# PowerNode.net
KiCad netlist of a schematic drawn in EAGLE
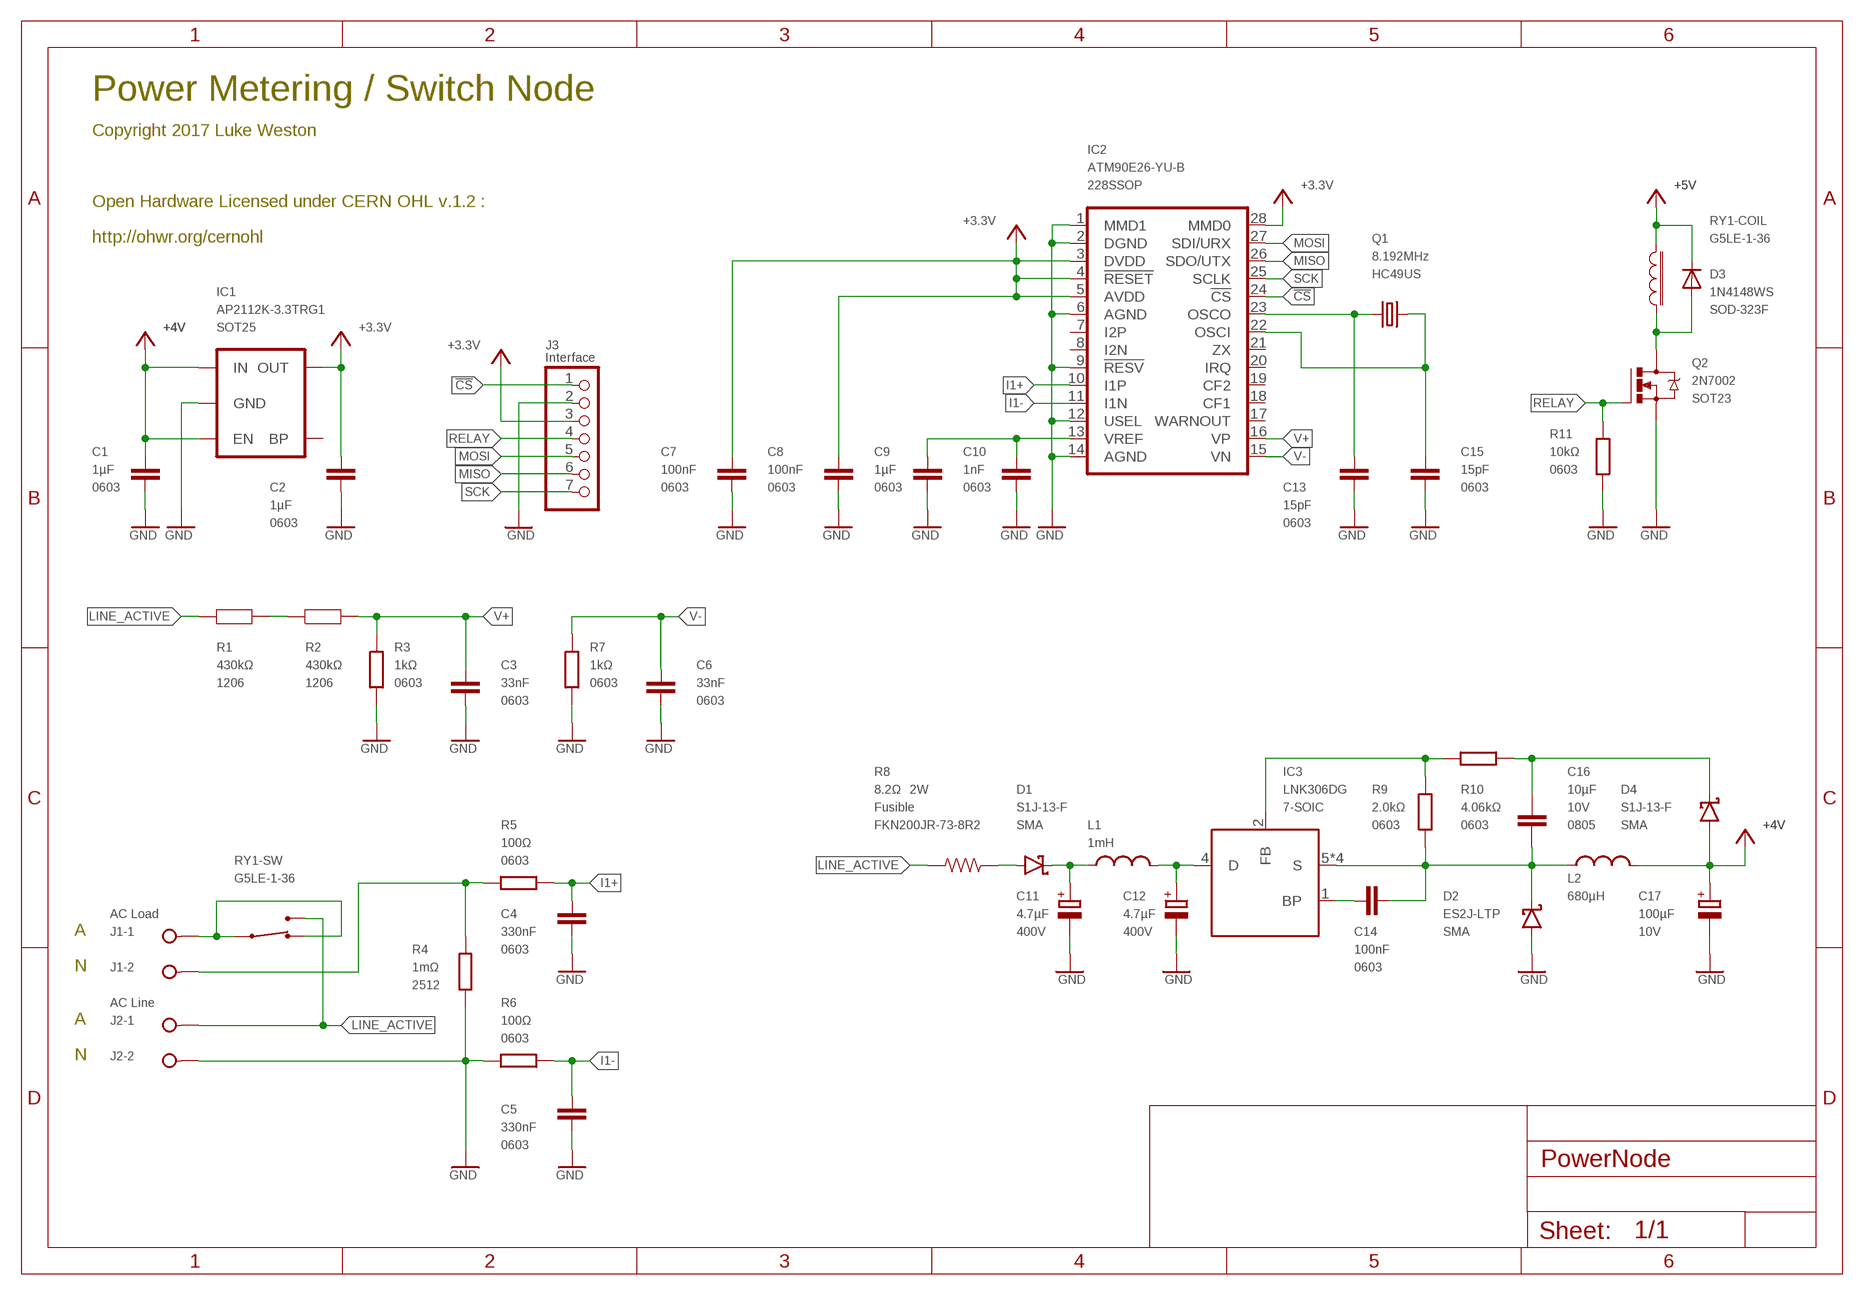
[diagram p0: schematic, sheet 1]

(export (version "E")
  (design (tool "Eeschema 10.0.6"))
  (components
    (comp (ref "C1")
      (value "1µF")
      (footprint "eagle-import:0603")
      (fields (field (name "PACKAGE") "0603"))
      (libsource (lib "eagle-import") (part "C0603"))
    )
    (comp (ref "C2")
      (value "1µF")
      (footprint "eagle-import:0603")
      (fields (field (name "PACKAGE") "0603"))
      (libsource (lib "eagle-import") (part "C0603"))
    )
    (comp (ref "C3")
      (value "33nF")
      (footprint "eagle-import:0603")
      (fields (field (name "PACKAGE") "0603"))
      (libsource (lib "eagle-import") (part "C0603"))
    )
    (comp (ref "C4")
      (value "330nF")
      (footprint "eagle-import:0603")
      (fields (field (name "PACKAGE") "0603"))
      (libsource (lib "eagle-import") (part "C0603"))
    )
    (comp (ref "C5")
      (value "330nF")
      (footprint "eagle-import:0603")
      (fields (field (name "PACKAGE") "0603"))
      (libsource (lib "eagle-import") (part "C0603"))
    )
    (comp (ref "C6")
      (value "33nF")
      (footprint "eagle-import:0603")
      (fields (field (name "PACKAGE") "0603"))
      (libsource (lib "eagle-import") (part "C0603"))
    )
    (comp (ref "C7")
      (value "100nF")
      (footprint "eagle-import:0603")
      (fields (field (name "PACKAGE") "0603"))
      (libsource (lib "eagle-import") (part "C0603"))
    )
    (comp (ref "C8")
      (value "100nF")
      (footprint "eagle-import:0603")
      (fields (field (name "PACKAGE") "0603"))
      (libsource (lib "eagle-import") (part "C0603"))
    )
    (comp (ref "C9")
      (value "1µF")
      (footprint "eagle-import:0603")
      (fields (field (name "PACKAGE") "0603"))
      (libsource (lib "eagle-import") (part "C0603"))
    )
    (comp (ref "C10")
      (value "1nF")
      (footprint "eagle-import:0603")
      (fields (field (name "PACKAGE") "0603"))
      (libsource (lib "eagle-import") (part "C0603"))
    )
    (comp (ref "C11")
      (value "4.7µF")
      (footprint "eagle-import:ELECTRO-LARGE")
      (fields (field (name "VOLTAGE") "400V"))
      (libsource (lib "eagle-import") (part "ELECTROLYTIC3.5MM"))
    )
    (comp (ref "C12")
      (value "4.7µF")
      (footprint "eagle-import:ELECTRO-LARGE")
      (fields (field (name "VOLTAGE") "400V"))
      (libsource (lib "eagle-import") (part "ELECTROLYTIC3.5MM"))
    )
    (comp (ref "C13")
      (value "15pF")
      (footprint "eagle-import:0603")
      (fields (field (name "PACKAGE") "0603"))
      (libsource (lib "eagle-import") (part "C0603"))
    )
    (comp (ref "C14")
      (value "100nF")
      (footprint "eagle-import:0603")
      (fields (field (name "PACKAGE") "0603"))
      (libsource (lib "eagle-import") (part "C0603"))
    )
    (comp (ref "C15")
      (value "15pF")
      (footprint "eagle-import:0603")
      (fields (field (name "PACKAGE") "0603"))
      (libsource (lib "eagle-import") (part "C0603"))
    )
    (comp (ref "C16")
      (value "10µF")
      (footprint "eagle-import:0805")
      (fields (field (name "PACKAGE") "0805") (field (name "VOLTAGE") "10V"))
      (libsource (lib "eagle-import") (part "CAP0805"))
    )
    (comp (ref "C17")
      (value "100µF")
      (footprint "eagle-import:ELECTRO-SMALL")
      (fields (field (name "VOLTAGE") "10V"))
      (libsource (lib "eagle-import") (part "ELECTROLYTIC2MM"))
    )
    (comp (ref "D1")
      (value "S1J-13-F")
      (footprint "eagle-import:SMA")
      (fields (field (name "PACKAGE") "SMA"))
      (libsource (lib "eagle-import") (part "SCHOTTKY-SMA"))
    )
    (comp (ref "D2")
      (value "ES2J-LTP")
      (footprint "eagle-import:SMA")
      (fields (field (name "PACKAGE") "SMA"))
      (libsource (lib "eagle-import") (part "SCHOTTKY-SMA"))
    )
    (comp (ref "D3")
      (value "1N4148WS")
      (footprint "eagle-import:SOD-323")
      (fields (field (name "PACKAGE") "SOD-323F"))
      (libsource (lib "eagle-import") (part "DIODESOD"))
    )
    (comp (ref "D4")
      (value "S1J-13-F")
      (footprint "eagle-import:SMA")
      (fields (field (name "PACKAGE") "SMA"))
      (libsource (lib "eagle-import") (part "SCHOTTKY-SMA"))
    )
    (comp (ref "IC1")
      (value "AP2112K-3.3TRG1")
      (footprint "eagle-import:SOT23-5")
      (fields (field (name "PACKAGE") "SOT25"))
      (libsource (lib "eagle-import") (part "V_REG_LDOSMD"))
    )
    (comp (ref "IC2")
      (value "ATM90E26-YU-B")
      (footprint "eagle-import:SSOP-28")
      (fields (field (name "PACKAGE") "228SSOP"))
      (libsource (lib "eagle-import") (part "ATM90E26"))
    )
    (comp (ref "IC3")
      (value "LNK306DG")
      (footprint "eagle-import:SO-8C")
      (fields (field (name "PACKAGE") "7-SOIC"))
      (libsource (lib "eagle-import") (part "LNK304"))
    )
    (comp (ref "J1")
      (value "AC Load")
      (footprint "eagle-import:W237-132")
      (libsource (lib "eagle-import") (part "W237-02P"))
    )
    (comp (ref "J2")
      (value "AC Line")
      (footprint "eagle-import:W237-132")
      (libsource (lib "eagle-import") (part "W237-02P"))
    )
    (comp (ref "J3")
      (value "Interface")
      (footprint "eagle-import:1X07")
      (libsource (lib "eagle-import") (part "PINHD-1X7"))
    )
    (comp (ref "L1")
      (value "1mH")
      (footprint "eagle-import:RLB0608")
      (libsource (lib "eagle-import") (part "LRLB0608"))
    )
    (comp (ref "L2")
      (value "680µH")
      (footprint "eagle-import:RLB0914")
      (libsource (lib "eagle-import") (part "LRLB0914"))
    )
    (comp (ref "Q1")
      (value "8.192MHz")
      (footprint "eagle-import:HC49_S")
      (fields (field (name "PACKAGE") "HC49US") (field (name "PARTNO") "9B-4.096MBBK-B"))
      (libsource (lib "eagle-import") (part "CRYSTALHC49S"))
    )
    (comp (ref "Q2")
      (value "2N7002")
      (footprint "eagle-import:SOT23-3")
      (fields (field (name "PACKAGE") "SOT23"))
      (libsource (lib "eagle-import") (part "2N7002"))
    )
    (comp (ref "R1")
      (value "430kΩ")
      (footprint "eagle-import:1206")
      (fields (field (name "PACKAGE") "1206") (field (name "POWER") "1/4W") (field (name "TOLERANCE") "1%"))
      (libsource (lib "eagle-import") (part "RESISTOR1206"))
    )
    (comp (ref "R2")
      (value "430kΩ")
      (footprint "eagle-import:1206")
      (fields (field (name "PACKAGE") "1206") (field (name "POWER") "1/4W") (field (name "TOLERANCE") "1%"))
      (libsource (lib "eagle-import") (part "RESISTOR1206"))
    )
    (comp (ref "R3")
      (value "1kΩ")
      (footprint "eagle-import:0603")
      (fields (field (name "PACKAGE") "0603"))
      (libsource (lib "eagle-import") (part "R0603"))
    )
    (comp (ref "R4")
      (value "1mΩ")
      (footprint "eagle-import:R2512")
      (fields (field (name "PACKAGE") "2512") (field (name "POWER") "1W") (field (name "TOLERANCE") "1%"))
      (libsource (lib "eagle-import") (part "R-EU_R2512"))
    )
    (comp (ref "R5")
      (value "100Ω")
      (footprint "eagle-import:0603")
      (fields (field (name "PACKAGE") "0603"))
      (libsource (lib "eagle-import") (part "R0603"))
    )
    (comp (ref "R6")
      (value "100Ω")
      (footprint "eagle-import:0603")
      (fields (field (name "PACKAGE") "0603"))
      (libsource (lib "eagle-import") (part "R0603"))
    )
    (comp (ref "R7")
      (value "1kΩ")
      (footprint "eagle-import:0603")
      (fields (field (name "PACKAGE") "0603"))
      (libsource (lib "eagle-import") (part "R0603"))
    )
    (comp (ref "R8")
      (value "8.2Ω")
      (footprint "eagle-import:FKN200JR-73")
      (fields
        (field (name "FOO") "Fusible")
        (field (name "ID") "FKN200JR-73-8R2")
        (field (name "POWER") "2W")
      )
      (libsource (lib "eagle-import") (part "RESISTORFKN200JR-73"))
    )
    (comp (ref "R9")
      (value "2.0kΩ")
      (footprint "eagle-import:0603")
      (fields (field (name "PACKAGE") "0603"))
      (libsource (lib "eagle-import") (part "R0603"))
    )
    (comp (ref "R10")
      (value "4.06kΩ")
      (footprint "eagle-import:0603")
      (fields (field (name "PACKAGE") "0603"))
      (libsource (lib "eagle-import") (part "R0603"))
    )
    (comp (ref "R11")
      (value "10kΩ")
      (footprint "eagle-import:0603")
      (fields (field (name "PACKAGE") "0603"))
      (libsource (lib "eagle-import") (part "R0603"))
    )
    (comp (ref "RY1")
      (value "G5LE-1-36")
      (footprint "eagle-import:G5LE")
      (libsource (lib "eagle-import") (part "G5LE"))
    )
  )
  (nets
    (net (code "1") (name "+3.3V") (class "Default")
      (node (ref "C2") (pin "1") (pinfunction "1_1") (pintype "passive"))
      (node (ref "C7") (pin "2") (pinfunction "2_2") (pintype "passive"))
      (node (ref "C8") (pin "2") (pinfunction "2_2") (pintype "passive"))
      (node (ref "IC1") (pin "5") (pinfunction "OUT_5") (pintype "passive"))
      (node (ref "IC2") (pin "28") (pinfunction "MMD0_28") (pintype "input"))
      (node (ref "IC2") (pin "3") (pinfunction "DVDD_3") (pintype "power_in"))
      (node (ref "IC2") (pin "4") (pinfunction "~{RESET}_4") (pintype "input"))
      (node (ref "IC2") (pin "5") (pinfunction "AVDD_5") (pintype "power_in"))
      (node (ref "J3") (pin "3") (pinfunction "3_3") (pintype "passive"))
    )
    (net (code "2") (name "/+4V") (class "Default")
      (node (ref "C1") (pin "1") (pinfunction "1_1") (pintype "passive"))
      (node (ref "C17") (pin "+") (pinfunction "+_+") (pintype "passive"))
      (node (ref "D3") (pin "1") (pinfunction "C_1") (pintype "passive"))
      (node (ref "D4") (pin "A") (pinfunction "A_A") (pintype "passive"))
      (node (ref "IC1") (pin "1") (pinfunction "IN_1") (pintype "input"))
      (node (ref "IC1") (pin "3") (pinfunction "EN_3") (pintype "input"))
      (node (ref "L2") (pin "2") (pinfunction "2_2") (pintype "bidirectional"))
      (node (ref "RY1") (pin "COIL1") (pinfunction "1_COIL1") (pintype "bidirectional"))
    )
    (net (code "3") (name "/GND") (class "Default")
      (node (ref "C1") (pin "2") (pinfunction "2_2") (pintype "passive"))
      (node (ref "C10") (pin "1") (pinfunction "1_1") (pintype "passive"))
      (node (ref "C11") (pin "-") (pinfunction "-_-") (pintype "passive"))
      (node (ref "C12") (pin "-") (pinfunction "-_-") (pintype "passive"))
      (node (ref "C13") (pin "1") (pinfunction "1_1") (pintype "passive"))
      (node (ref "C15") (pin "1") (pinfunction "1_1") (pintype "passive"))
      (node (ref "C17") (pin "-") (pinfunction "-_-") (pintype "passive"))
      (node (ref "C2") (pin "2") (pinfunction "2_2") (pintype "passive"))
      (node (ref "C3") (pin "1") (pinfunction "1_1") (pintype "passive"))
      (node (ref "C4") (pin "1") (pinfunction "1_1") (pintype "passive"))
      (node (ref "C5") (pin "1") (pinfunction "1_1") (pintype "passive"))
      (node (ref "C6") (pin "1") (pinfunction "1_1") (pintype "passive"))
      (node (ref "C7") (pin "1") (pinfunction "1_1") (pintype "passive"))
      (node (ref "C8") (pin "1") (pinfunction "1_1") (pintype "passive"))
      (node (ref "C9") (pin "2") (pinfunction "2_2") (pintype "passive"))
      (node (ref "D2") (pin "A") (pinfunction "A_A") (pintype "passive"))
      (node (ref "IC1") (pin "2") (pinfunction "GND_2") (pintype "input"))
      (node (ref "IC2") (pin "1") (pinfunction "MMD1_1") (pintype "input"))
      (node (ref "IC2") (pin "12") (pinfunction "USEL_12") (pintype "input"))
      (node (ref "IC2") (pin "14") (pinfunction "AGND_14") (pintype "power_in"))
      (node (ref "IC2") (pin "2") (pinfunction "DGND_2") (pintype "power_in"))
      (node (ref "IC2") (pin "6") (pinfunction "AGND_6") (pintype "power_in"))
      (node (ref "IC2") (pin "9") (pinfunction "~{RESV}_9") (pintype "input"))
      (node (ref "J2") (pin "2") (pinfunction "KL_2") (pintype "passive"))
      (node (ref "J3") (pin "2") (pinfunction "2_2") (pintype "passive"))
      (node (ref "Q2") (pin "2") (pinfunction "S_2") (pintype "passive"))
      (node (ref "R11") (pin "1") (pinfunction "1_1") (pintype "passive"))
      (node (ref "R3") (pin "2") (pinfunction "2_2") (pintype "passive"))
      (node (ref "R4") (pin "1") (pinfunction "1_1") (pintype "passive"))
      (node (ref "R6") (pin "2") (pinfunction "2_2") (pintype "passive"))
      (node (ref "R7") (pin "2") (pinfunction "2_2") (pintype "passive"))
    )
    (net (code "4") (name "/~{CS}") (class "Default")
      (node (ref "IC2") (pin "24") (pinfunction "~{CS}_24") (pintype "input"))
      (node (ref "J3") (pin "1") (pinfunction "1_1") (pintype "passive"))
    )
    (net (code "5") (name "I1+") (class "Default")
      (node (ref "C4") (pin "2") (pinfunction "2_2") (pintype "passive"))
      (node (ref "IC2") (pin "10") (pinfunction "I1P_10") (pintype "input"))
      (node (ref "R5") (pin "1") (pinfunction "1_1") (pintype "passive"))
    )
    (net (code "6") (name "I1-") (class "Default")
      (node (ref "C5") (pin "2") (pinfunction "2_2") (pintype "passive"))
      (node (ref "IC2") (pin "11") (pinfunction "I1N_11") (pintype "input"))
      (node (ref "R6") (pin "1") (pinfunction "1_1") (pintype "passive"))
    )
    (net (code "7") (name "LINE_ACTIVE") (class "Default")
      (node (ref "J2") (pin "1") (pinfunction "KL_1") (pintype "passive"))
      (node (ref "R1") (pin "1") (pinfunction "1_1") (pintype "passive"))
      (node (ref "R8") (pin "1") (pinfunction "1_1") (pintype "bidirectional"))
      (node (ref "RY1") (pin "NO") (pinfunction "NO_NO") (pintype "passive"))
    )
    (net (code "8") (name "MISO") (class "Default")
      (node (ref "IC2") (pin "26") (pinfunction "SDO/UTX_26") (pintype "output"))
      (node (ref "J3") (pin "6") (pinfunction "6_6") (pintype "passive"))
    )
    (net (code "9") (name "MOSI") (class "Default")
      (node (ref "IC2") (pin "27") (pinfunction "SDI/URX_27") (pintype "input"))
      (node (ref "J3") (pin "5") (pinfunction "5_5") (pintype "passive"))
    )
    (net (code "10") (name "Net-(C11-Pad+)") (class "Default")
      (node (ref "C11") (pin "+") (pinfunction "+_+") (pintype "passive"))
      (node (ref "D1") (pin "K") (pinfunction "K_K") (pintype "passive"))
      (node (ref "L1") (pin "1") (pinfunction "1_1") (pintype "bidirectional"))
    )
    (net (code "11") (name "Net-(C14-Pad2)") (class "Default")
      (node (ref "C14") (pin "2") (pinfunction "2_2") (pintype "passive"))
      (node (ref "C16") (pin "1") (pinfunction "1_1") (pintype "passive"))
      (node (ref "D2") (pin "K") (pinfunction "K_K") (pintype "passive"))
      (node (ref "IC3") (pin "5") (pinfunction "S_5") (pintype "bidirectional"))
      (node (ref "IC3") (pin "6") (pinfunction "S_6") (pintype "bidirectional"))
      (node (ref "IC3") (pin "7") (pinfunction "S_7") (pintype "bidirectional"))
      (node (ref "IC3") (pin "8") (pinfunction "S_8") (pintype "bidirectional"))
      (node (ref "L2") (pin "1") (pinfunction "1_1") (pintype "bidirectional"))
      (node (ref "R9") (pin "1") (pinfunction "1_1") (pintype "passive"))
    )
    (net (code "12") (name "Net-(C16-Pad2)") (class "Default")
      (node (ref "C16") (pin "2") (pinfunction "2_2") (pintype "passive"))
      (node (ref "D4") (pin "K") (pinfunction "K_K") (pintype "passive"))
      (node (ref "R10") (pin "1") (pinfunction "1_1") (pintype "passive"))
    )
    (net (code "13") (name "Net-(D1-PadA)") (class "Default")
      (node (ref "D1") (pin "A") (pinfunction "A_A") (pintype "passive"))
      (node (ref "R8") (pin "2") (pinfunction "2_2") (pintype "bidirectional"))
    )
    (net (code "14") (name "Net-(D3-A)") (class "Default")
      (node (ref "D3") (pin "2") (pinfunction "A_2") (pintype "passive"))
      (node (ref "Q2") (pin "3") (pinfunction "D_3") (pintype "passive"))
      (node (ref "RY1") (pin "COIL2") (pinfunction "2_COIL2") (pintype "bidirectional"))
    )
    (net (code "15") (name "Net-(IC2-OSCI)") (class "Default")
      (node (ref "C15") (pin "2") (pinfunction "2_2") (pintype "passive"))
      (node (ref "IC2") (pin "22") (pinfunction "OSCI_22") (pintype "input"))
      (node (ref "Q1") (pin "2") (pinfunction "2_2") (pintype "passive"))
    )
    (net (code "16") (name "Net-(IC2-OSCO)") (class "Default")
      (node (ref "C13") (pin "2") (pinfunction "2_2") (pintype "passive"))
      (node (ref "IC2") (pin "23") (pinfunction "OSCO_23") (pintype "output"))
      (node (ref "Q1") (pin "1") (pinfunction "1_1") (pintype "passive"))
    )
    (net (code "17") (name "Net-(IC2-VREF)") (class "Default")
      (node (ref "C10") (pin "2") (pinfunction "2_2") (pintype "passive"))
      (node (ref "C9") (pin "1") (pinfunction "1_1") (pintype "passive"))
      (node (ref "IC2") (pin "13") (pinfunction "VREF_13") (pintype "power_in"))
    )
    (net (code "18") (name "Net-(IC3-BP)") (class "Default")
      (node (ref "C14") (pin "1") (pinfunction "1_1") (pintype "passive"))
      (node (ref "IC3") (pin "1") (pinfunction "BP_1") (pintype "bidirectional"))
    )
    (net (code "19") (name "Net-(IC3-D)") (class "Default")
      (node (ref "C12") (pin "+") (pinfunction "+_+") (pintype "passive"))
      (node (ref "IC3") (pin "4") (pinfunction "D_4") (pintype "bidirectional"))
      (node (ref "L1") (pin "2") (pinfunction "2_2") (pintype "bidirectional"))
    )
    (net (code "20") (name "Net-(IC3-FB)") (class "Default")
      (node (ref "IC3") (pin "2") (pinfunction "FB_2") (pintype "bidirectional"))
      (node (ref "R10") (pin "2") (pinfunction "2_2") (pintype "passive"))
      (node (ref "R9") (pin "2") (pinfunction "2_2") (pintype "passive"))
    )
    (net (code "21") (name "Net-(J1A-KL)") (class "Default")
      (node (ref "J1") (pin "1") (pinfunction "KL_1") (pintype "passive"))
      (node (ref "RY1") (pin "COM") (pinfunction "COM_COM") (pintype "passive"))
      (node (ref "RY1") (pin "NC") (pinfunction "NC_NC") (pintype "passive"))
    )
    (net (code "22") (name "Net-(J1B-KL)") (class "Default")
      (node (ref "J1") (pin "2") (pinfunction "KL_2") (pintype "passive"))
      (node (ref "R4") (pin "2") (pinfunction "2_2") (pintype "passive"))
      (node (ref "R5") (pin "2") (pinfunction "2_2") (pintype "passive"))
    )
    (net (code "23") (name "Net-(R1-Pad2)") (class "Default")
      (node (ref "R1") (pin "2") (pinfunction "2_2") (pintype "passive"))
      (node (ref "R2") (pin "1") (pinfunction "1_1") (pintype "passive"))
    )
    (net (code "24") (name "RELAY") (class "Default")
      (node (ref "J3") (pin "4") (pinfunction "4_4") (pintype "passive"))
      (node (ref "Q2") (pin "1") (pinfunction "G_1") (pintype "passive"))
      (node (ref "R11") (pin "2") (pinfunction "2_2") (pintype "passive"))
    )
    (net (code "25") (name "SCK") (class "Default")
      (node (ref "IC2") (pin "25") (pinfunction "SCLK_25") (pintype "input"))
      (node (ref "J3") (pin "7") (pinfunction "7_7") (pintype "passive"))
    )
    (net (code "26") (name "V+") (class "Default")
      (node (ref "C3") (pin "2") (pinfunction "2_2") (pintype "passive"))
      (node (ref "IC2") (pin "16") (pinfunction "VP_16") (pintype "input"))
      (node (ref "R2") (pin "2") (pinfunction "2_2") (pintype "passive"))
      (node (ref "R3") (pin "1") (pinfunction "1_1") (pintype "passive"))
    )
    (net (code "27") (name "V-") (class "Default")
      (node (ref "C6") (pin "2") (pinfunction "2_2") (pintype "passive"))
      (node (ref "IC2") (pin "15") (pinfunction "VN_15") (pintype "input"))
      (node (ref "R7") (pin "1") (pinfunction "1_1") (pintype "passive"))
    )
    (net (code "28") (name "unconnected-(IC1-BP-Pad4)") (class "Default")
      (node (ref "IC1") (pin "4") (pinfunction "BP_4") (pintype "input"))
    )
    (net (code "29") (name "unconnected-(IC2-CF1-Pad18)") (class "Default")
      (node (ref "IC2") (pin "18") (pinfunction "CF1_18") (pintype "output"))
    )
    (net (code "30") (name "unconnected-(IC2-CF2-Pad19)") (class "Default")
      (node (ref "IC2") (pin "19") (pinfunction "CF2_19") (pintype "output"))
    )
    (net (code "31") (name "unconnected-(IC2-I2N-Pad8)") (class "Default")
      (node (ref "IC2") (pin "8") (pinfunction "I2N_8") (pintype "input"))
    )
    (net (code "32") (name "unconnected-(IC2-I2P-Pad7)") (class "Default")
      (node (ref "IC2") (pin "7") (pinfunction "I2P_7") (pintype "input"))
    )
    (net (code "33") (name "unconnected-(IC2-IRQ-Pad20)") (class "Default")
      (node (ref "IC2") (pin "20") (pinfunction "IRQ_20") (pintype "output"))
    )
    (net (code "34") (name "unconnected-(IC2-WARNOUT-Pad17)") (class "Default")
      (node (ref "IC2") (pin "17") (pinfunction "WARNOUT_17") (pintype "output"))
    )
    (net (code "35") (name "unconnected-(IC2-ZX-Pad21)") (class "Default")
      (node (ref "IC2") (pin "21") (pinfunction "ZX_21") (pintype "bidirectional"))
    )
  )
)
